# PCB-DISPARRAY4a.net
KiCad netlist of a schematic drawn in EAGLE
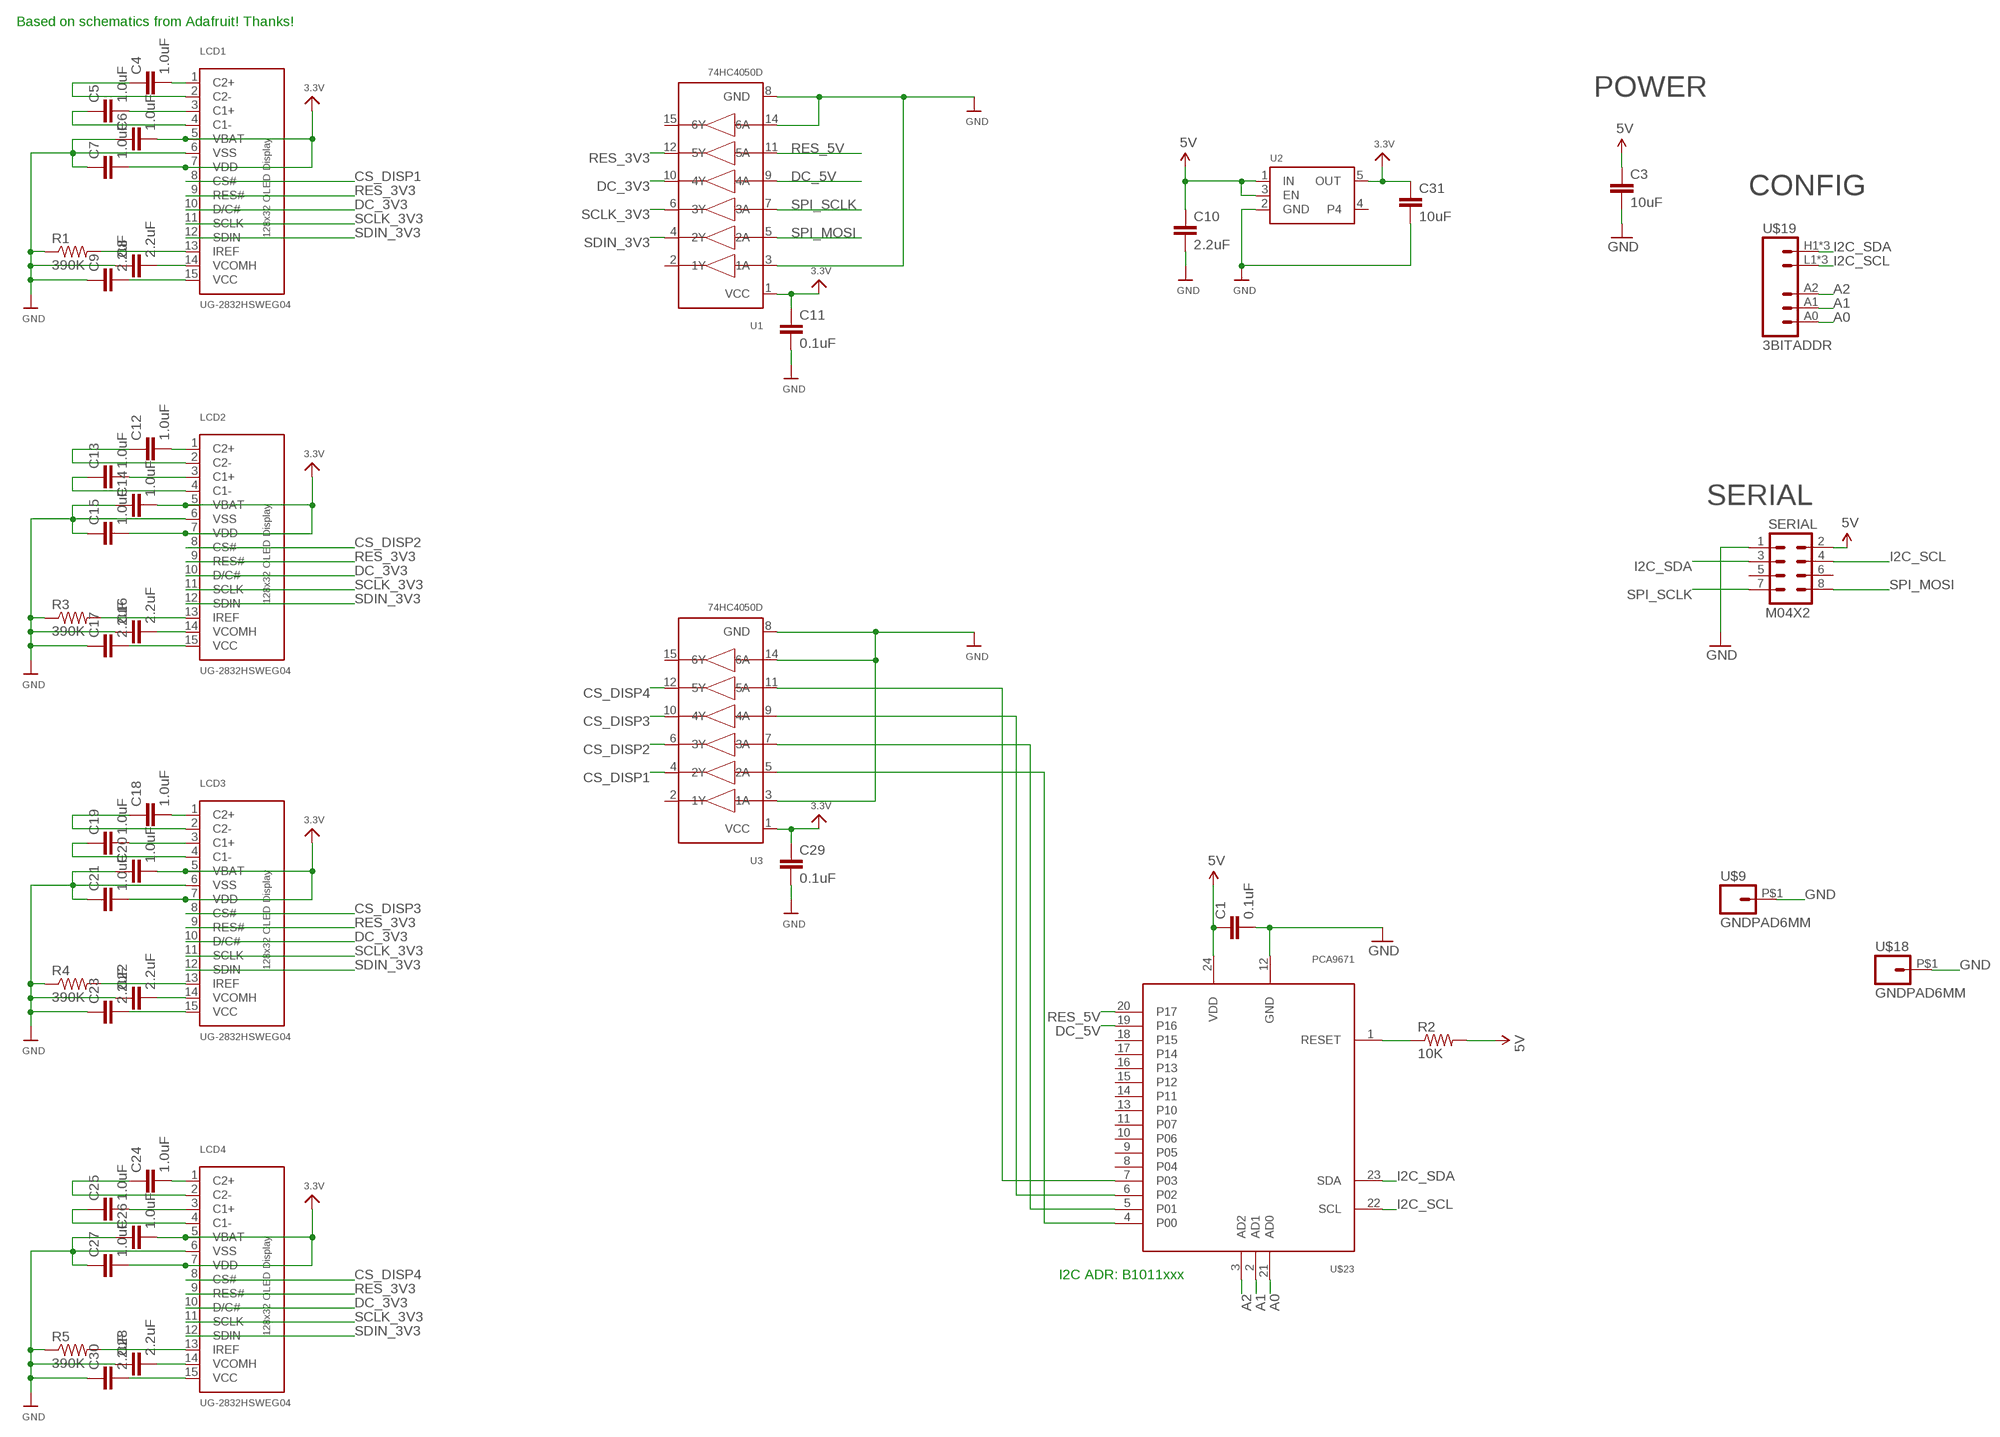
[diagram p0: schematic, sheet 1]

(export (version "E")
  (design (tool "Eeschema 10.0.6"))
  (components
    (comp (ref "C1")
      (value "0.1uF")
      (footprint "eagle-import:0603-CAP")
      (libsource (lib "eagle-import") (part "CAP0603-CAP"))
    )
    (comp (ref "C3")
      (value "10uF")
      (footprint "eagle-import:0805")
      (libsource (lib "eagle-import") (part "CAP0805"))
    )
    (comp (ref "C4")
      (value "1.0uF")
      (footprint "eagle-import:0603-CAP")
      (libsource (lib "eagle-import") (part "CAP0603-CAP"))
    )
    (comp (ref "C5")
      (value "1.0uF")
      (footprint "eagle-import:0603-CAP")
      (libsource (lib "eagle-import") (part "CAP0603-CAP"))
    )
    (comp (ref "C6")
      (value "1.0uF")
      (footprint "eagle-import:0603-CAP")
      (libsource (lib "eagle-import") (part "CAP0603-CAP"))
    )
    (comp (ref "C7")
      (value "1.0uF")
      (footprint "eagle-import:0603-CAP")
      (libsource (lib "eagle-import") (part "CAP0603-CAP"))
    )
    (comp (ref "C8")
      (value "2.2uF")
      (footprint "eagle-import:0603-CAP")
      (libsource (lib "eagle-import") (part "CAP0603-CAP"))
    )
    (comp (ref "C9")
      (value "2.2uF")
      (footprint "eagle-import:0603-CAP")
      (libsource (lib "eagle-import") (part "CAP0603-CAP"))
    )
    (comp (ref "C10")
      (value "2.2uF")
      (footprint "eagle-import:0805")
      (libsource (lib "eagle-import") (part "CAP0805"))
    )
    (comp (ref "C11")
      (value "0.1uF")
      (footprint "eagle-import:0603-CAP")
      (libsource (lib "eagle-import") (part "CAP0603-CAP"))
    )
    (comp (ref "C12")
      (value "1.0uF")
      (footprint "eagle-import:0603-CAP")
      (libsource (lib "eagle-import") (part "CAP0603-CAP"))
    )
    (comp (ref "C13")
      (value "1.0uF")
      (footprint "eagle-import:0603-CAP")
      (libsource (lib "eagle-import") (part "CAP0603-CAP"))
    )
    (comp (ref "C14")
      (value "1.0uF")
      (footprint "eagle-import:0603-CAP")
      (libsource (lib "eagle-import") (part "CAP0603-CAP"))
    )
    (comp (ref "C15")
      (value "1.0uF")
      (footprint "eagle-import:0603-CAP")
      (libsource (lib "eagle-import") (part "CAP0603-CAP"))
    )
    (comp (ref "C16")
      (value "2.2uF")
      (footprint "eagle-import:0603-CAP")
      (libsource (lib "eagle-import") (part "CAP0603-CAP"))
    )
    (comp (ref "C17")
      (value "2.2uF")
      (footprint "eagle-import:0603-CAP")
      (libsource (lib "eagle-import") (part "CAP0603-CAP"))
    )
    (comp (ref "C18")
      (value "1.0uF")
      (footprint "eagle-import:0603-CAP")
      (libsource (lib "eagle-import") (part "CAP0603-CAP"))
    )
    (comp (ref "C19")
      (value "1.0uF")
      (footprint "eagle-import:0603-CAP")
      (libsource (lib "eagle-import") (part "CAP0603-CAP"))
    )
    (comp (ref "C20")
      (value "1.0uF")
      (footprint "eagle-import:0603-CAP")
      (libsource (lib "eagle-import") (part "CAP0603-CAP"))
    )
    (comp (ref "C21")
      (value "1.0uF")
      (footprint "eagle-import:0603-CAP")
      (libsource (lib "eagle-import") (part "CAP0603-CAP"))
    )
    (comp (ref "C22")
      (value "2.2uF")
      (footprint "eagle-import:0603-CAP")
      (libsource (lib "eagle-import") (part "CAP0603-CAP"))
    )
    (comp (ref "C23")
      (value "2.2uF")
      (footprint "eagle-import:0603-CAP")
      (libsource (lib "eagle-import") (part "CAP0603-CAP"))
    )
    (comp (ref "C24")
      (value "1.0uF")
      (footprint "eagle-import:0603-CAP")
      (libsource (lib "eagle-import") (part "CAP0603-CAP"))
    )
    (comp (ref "C25")
      (value "1.0uF")
      (footprint "eagle-import:0603-CAP")
      (libsource (lib "eagle-import") (part "CAP0603-CAP"))
    )
    (comp (ref "C26")
      (value "1.0uF")
      (footprint "eagle-import:0603-CAP")
      (libsource (lib "eagle-import") (part "CAP0603-CAP"))
    )
    (comp (ref "C27")
      (value "1.0uF")
      (footprint "eagle-import:0603-CAP")
      (libsource (lib "eagle-import") (part "CAP0603-CAP"))
    )
    (comp (ref "C28")
      (value "2.2uF")
      (footprint "eagle-import:0603-CAP")
      (libsource (lib "eagle-import") (part "CAP0603-CAP"))
    )
    (comp (ref "C29")
      (value "0.1uF")
      (footprint "eagle-import:0603-CAP")
      (libsource (lib "eagle-import") (part "CAP0603-CAP"))
    )
    (comp (ref "C30")
      (value "2.2uF")
      (footprint "eagle-import:0603-CAP")
      (libsource (lib "eagle-import") (part "CAP0603-CAP"))
    )
    (comp (ref "C31")
      (value "10uF")
      (footprint "eagle-import:0805")
      (libsource (lib "eagle-import") (part "CAP0805"))
    )
    (comp (ref "LCD1")
      (value "UG-2832HSWEG04")
      (footprint "eagle-import:UG-2832HSWEG04_WRAPAROUND")
      (libsource (lib "eagle-import") (part "OLED_UG-2832HSWEG04WRAPAROUND"))
    )
    (comp (ref "LCD2")
      (value "UG-2832HSWEG04")
      (footprint "eagle-import:UG-2832HSWEG04_WRAPAROUND")
      (libsource (lib "eagle-import") (part "OLED_UG-2832HSWEG04WRAPAROUND"))
    )
    (comp (ref "LCD3")
      (value "UG-2832HSWEG04")
      (footprint "eagle-import:UG-2832HSWEG04_WRAPAROUND")
      (libsource (lib "eagle-import") (part "OLED_UG-2832HSWEG04WRAPAROUND"))
    )
    (comp (ref "LCD4")
      (value "UG-2832HSWEG04")
      (footprint "eagle-import:UG-2832HSWEG04_WRAPAROUND")
      (libsource (lib "eagle-import") (part "OLED_UG-2832HSWEG04WRAPAROUND"))
    )
    (comp (ref "R1")
      (value "390K")
      (footprint "eagle-import:0603-RES")
      (libsource (lib "eagle-import") (part "RESISTOR0603-RES"))
    )
    (comp (ref "R2")
      (value "10K")
      (footprint "eagle-import:0603-RES")
      (libsource (lib "eagle-import") (part "RESISTOR0603-RES"))
    )
    (comp (ref "R3")
      (value "390K")
      (footprint "eagle-import:0603-RES")
      (libsource (lib "eagle-import") (part "RESISTOR0603-RES"))
    )
    (comp (ref "R4")
      (value "390K")
      (footprint "eagle-import:0603-RES")
      (libsource (lib "eagle-import") (part "RESISTOR0603-RES"))
    )
    (comp (ref "R5")
      (value "390K")
      (footprint "eagle-import:0603-RES")
      (libsource (lib "eagle-import") (part "RESISTOR0603-RES"))
    )
    (comp (ref "SERIAL")
      (value "M04X2")
      (footprint "eagle-import:2X4")
      (libsource (lib "eagle-import") (part "M04X2"))
    )
    (comp (ref "U$9")
      (value "GNDPAD6MM")
      (footprint "eagle-import:3.2MMPAD6MM")
      (libsource (lib "eagle-import") (part "GNDPAD6MM"))
    )
    (comp (ref "U$18")
      (value "GNDPAD6MM")
      (footprint "eagle-import:3.2MMPAD6MM")
      (libsource (lib "eagle-import") (part "GNDPAD6MM"))
    )
    (comp (ref "U$19")
      (value "3BITADDR")
      (footprint "eagle-import:3BITADDR")
      (libsource (lib "eagle-import") (part "3BITADDR"))
    )
    (comp (ref "U$23")
      (value "PCA9671")
      (footprint "eagle-import:TSSOP24")
      (libsource (lib "eagle-import") (part "PCA9671"))
    )
    (comp (ref "U1")
      (value "74HC4050D")
      (footprint "eagle-import:TSSOP16")
      (libsource (lib "eagle-import") (part "74HC4050DTSSOP16"))
    )
    (comp (ref "U2")
      (value "VREG_SOT23-5")
      (footprint "eagle-import:SOT23-5")
      (libsource (lib "eagle-import") (part "VREG_SOT23-5"))
    )
    (comp (ref "U3")
      (value "74HC4050D")
      (footprint "eagle-import:TSSOP16")
      (libsource (lib "eagle-import") (part "74HC4050DTSSOP16"))
    )
  )
  (nets
    (net (code "1") (name "3.3V") (class "Default")
      (node (ref "C11") (pin "1") (pinfunction "1_1") (pintype "passive"))
      (node (ref "C14") (pin "2") (pinfunction "2_2") (pintype "passive"))
      (node (ref "C15") (pin "2") (pinfunction "2_2") (pintype "passive"))
      (node (ref "C20") (pin "2") (pinfunction "2_2") (pintype "passive"))
      (node (ref "C21") (pin "2") (pinfunction "2_2") (pintype "passive"))
      (node (ref "C26") (pin "2") (pinfunction "2_2") (pintype "passive"))
      (node (ref "C27") (pin "2") (pinfunction "2_2") (pintype "passive"))
      (node (ref "C29") (pin "1") (pinfunction "1_1") (pintype "passive"))
      (node (ref "C31") (pin "1") (pinfunction "1_1") (pintype "passive"))
      (node (ref "C6") (pin "2") (pinfunction "2_2") (pintype "passive"))
      (node (ref "C7") (pin "2") (pinfunction "2_2") (pintype "passive"))
      (node (ref "LCD1") (pin "5") (pinfunction "VBAT_5") (pintype "bidirectional"))
      (node (ref "LCD1") (pin "7") (pinfunction "VDD_7") (pintype "bidirectional"))
      (node (ref "LCD2") (pin "5") (pinfunction "VBAT_5") (pintype "bidirectional"))
      (node (ref "LCD2") (pin "7") (pinfunction "VDD_7") (pintype "bidirectional"))
      (node (ref "LCD3") (pin "5") (pinfunction "VBAT_5") (pintype "bidirectional"))
      (node (ref "LCD3") (pin "7") (pinfunction "VDD_7") (pintype "bidirectional"))
      (node (ref "LCD4") (pin "5") (pinfunction "VBAT_5") (pintype "bidirectional"))
      (node (ref "LCD4") (pin "7") (pinfunction "VDD_7") (pintype "bidirectional"))
      (node (ref "U1") (pin "1") (pinfunction "VCC_1") (pintype "bidirectional"))
      (node (ref "U2") (pin "5") (pinfunction "OUT_5") (pintype "bidirectional"))
      (node (ref "U3") (pin "1") (pinfunction "VCC_1") (pintype "bidirectional"))
    )
    (net (code "2") (name "5V") (class "Default")
      (node (ref "C1") (pin "1") (pinfunction "1_1") (pintype "passive"))
      (node (ref "C10") (pin "1") (pinfunction "1_1") (pintype "passive"))
      (node (ref "C3") (pin "1") (pinfunction "1_1") (pintype "passive"))
      (node (ref "R2") (pin "2") (pinfunction "2_2") (pintype "passive"))
      (node (ref "SERIAL") (pin "2") (pinfunction "2_2") (pintype "passive"))
      (node (ref "U$23") (pin "24") (pinfunction "VDD_24") (pintype "power_in"))
      (node (ref "U2") (pin "1") (pinfunction "IN_1") (pintype "bidirectional"))
      (node (ref "U2") (pin "3") (pinfunction "EN_3") (pintype "bidirectional"))
    )
    (net (code "3") (name "A0") (class "Default")
      (node (ref "U$19") (pin "A0") (pinfunction "A0_A0") (pintype "passive"))
      (node (ref "U$23") (pin "21") (pinfunction "AD0_21") (pintype "input"))
    )
    (net (code "4") (name "A1") (class "Default")
      (node (ref "U$19") (pin "A1") (pinfunction "A1_A1") (pintype "passive"))
      (node (ref "U$23") (pin "2") (pinfunction "AD1_2") (pintype "input"))
    )
    (net (code "5") (name "A2") (class "Default")
      (node (ref "U$19") (pin "A2") (pinfunction "A2_A2") (pintype "passive"))
      (node (ref "U$23") (pin "3") (pinfunction "AD2_3") (pintype "input"))
    )
    (net (code "6") (name "CS_DISP1") (class "Default")
      (node (ref "LCD1") (pin "8") (pinfunction "CS#_8") (pintype "bidirectional"))
      (node (ref "U3") (pin "4") (pinfunction "2Y_4") (pintype "bidirectional"))
    )
    (net (code "7") (name "CS_DISP2") (class "Default")
      (node (ref "LCD2") (pin "8") (pinfunction "CS#_8") (pintype "bidirectional"))
      (node (ref "U3") (pin "6") (pinfunction "3Y_6") (pintype "bidirectional"))
    )
    (net (code "8") (name "CS_DISP3") (class "Default")
      (node (ref "LCD3") (pin "8") (pinfunction "CS#_8") (pintype "bidirectional"))
      (node (ref "U3") (pin "10") (pinfunction "4Y_10") (pintype "bidirectional"))
    )
    (net (code "9") (name "CS_DISP4") (class "Default")
      (node (ref "LCD4") (pin "8") (pinfunction "CS#_8") (pintype "bidirectional"))
      (node (ref "U3") (pin "12") (pinfunction "5Y_12") (pintype "bidirectional"))
    )
    (net (code "10") (name "DC_3V3") (class "Default")
      (node (ref "LCD1") (pin "10") (pinfunction "D/C#_10") (pintype "bidirectional"))
      (node (ref "LCD2") (pin "10") (pinfunction "D/C#_10") (pintype "bidirectional"))
      (node (ref "LCD3") (pin "10") (pinfunction "D/C#_10") (pintype "bidirectional"))
      (node (ref "LCD4") (pin "10") (pinfunction "D/C#_10") (pintype "bidirectional"))
      (node (ref "U1") (pin "10") (pinfunction "4Y_10") (pintype "bidirectional"))
    )
    (net (code "11") (name "DC_5V") (class "Default")
      (node (ref "U$23") (pin "19") (pinfunction "P16_19") (pintype "output"))
      (node (ref "U1") (pin "9") (pinfunction "4A_9") (pintype "bidirectional"))
    )
    (net (code "12") (name "GND") (class "Default")
      (node (ref "C1") (pin "2") (pinfunction "2_2") (pintype "passive"))
      (node (ref "C10") (pin "2") (pinfunction "2_2") (pintype "passive"))
      (node (ref "C11") (pin "2") (pinfunction "2_2") (pintype "passive"))
      (node (ref "C14") (pin "1") (pinfunction "1_1") (pintype "passive"))
      (node (ref "C15") (pin "1") (pinfunction "1_1") (pintype "passive"))
      (node (ref "C16") (pin "1") (pinfunction "1_1") (pintype "passive"))
      (node (ref "C17") (pin "1") (pinfunction "1_1") (pintype "passive"))
      (node (ref "C20") (pin "1") (pinfunction "1_1") (pintype "passive"))
      (node (ref "C21") (pin "1") (pinfunction "1_1") (pintype "passive"))
      (node (ref "C22") (pin "1") (pinfunction "1_1") (pintype "passive"))
      (node (ref "C23") (pin "1") (pinfunction "1_1") (pintype "passive"))
      (node (ref "C26") (pin "1") (pinfunction "1_1") (pintype "passive"))
      (node (ref "C27") (pin "1") (pinfunction "1_1") (pintype "passive"))
      (node (ref "C28") (pin "1") (pinfunction "1_1") (pintype "passive"))
      (node (ref "C29") (pin "2") (pinfunction "2_2") (pintype "passive"))
      (node (ref "C3") (pin "2") (pinfunction "2_2") (pintype "passive"))
      (node (ref "C30") (pin "1") (pinfunction "1_1") (pintype "passive"))
      (node (ref "C31") (pin "2") (pinfunction "2_2") (pintype "passive"))
      (node (ref "C6") (pin "1") (pinfunction "1_1") (pintype "passive"))
      (node (ref "C7") (pin "1") (pinfunction "1_1") (pintype "passive"))
      (node (ref "C8") (pin "1") (pinfunction "1_1") (pintype "passive"))
      (node (ref "C9") (pin "1") (pinfunction "1_1") (pintype "passive"))
      (node (ref "LCD1") (pin "6") (pinfunction "VSS_6") (pintype "bidirectional"))
      (node (ref "LCD2") (pin "6") (pinfunction "VSS_6") (pintype "bidirectional"))
      (node (ref "LCD3") (pin "6") (pinfunction "VSS_6") (pintype "bidirectional"))
      (node (ref "LCD4") (pin "6") (pinfunction "VSS_6") (pintype "bidirectional"))
      (node (ref "R1") (pin "1") (pinfunction "1_1") (pintype "passive"))
      (node (ref "R3") (pin "1") (pinfunction "1_1") (pintype "passive"))
      (node (ref "R4") (pin "1") (pinfunction "1_1") (pintype "passive"))
      (node (ref "R5") (pin "1") (pinfunction "1_1") (pintype "passive"))
      (node (ref "SERIAL") (pin "1") (pinfunction "1_1") (pintype "passive"))
      (node (ref "U$18") (pin "P$1") (pinfunction "1_P$1") (pintype "passive"))
      (node (ref "U$23") (pin "12") (pinfunction "GND_12") (pintype "power_in"))
      (node (ref "U$9") (pin "P$1") (pinfunction "1_P$1") (pintype "passive"))
      (node (ref "U1") (pin "14") (pinfunction "6A_14") (pintype "bidirectional"))
      (node (ref "U1") (pin "3") (pinfunction "1A_3") (pintype "bidirectional"))
      (node (ref "U1") (pin "8") (pinfunction "GND_8") (pintype "bidirectional"))
      (node (ref "U2") (pin "2") (pinfunction "GND_2") (pintype "bidirectional"))
      (node (ref "U3") (pin "14") (pinfunction "6A_14") (pintype "bidirectional"))
      (node (ref "U3") (pin "3") (pinfunction "1A_3") (pintype "bidirectional"))
      (node (ref "U3") (pin "8") (pinfunction "GND_8") (pintype "bidirectional"))
    )
    (net (code "13") (name "I2C_SCL") (class "Default")
      (node (ref "SERIAL") (pin "4") (pinfunction "4_4") (pintype "passive"))
      (node (ref "U$19") (pin "L1") (pinfunction "GND_L1") (pintype "passive"))
      (node (ref "U$19") (pin "L2") (pinfunction "GND_L2") (pintype "passive"))
      (node (ref "U$19") (pin "L3") (pinfunction "GND_L3") (pintype "passive"))
      (node (ref "U$23") (pin "22") (pinfunction "SCL_22") (pintype "input"))
    )
    (net (code "14") (name "I2C_SDA") (class "Default")
      (node (ref "SERIAL") (pin "3") (pinfunction "3_3") (pintype "passive"))
      (node (ref "U$19") (pin "H1") (pinfunction "VCC_H1") (pintype "passive"))
      (node (ref "U$19") (pin "H2") (pinfunction "VCC_H2") (pintype "passive"))
      (node (ref "U$19") (pin "H3") (pinfunction "VCC_H3") (pintype "passive"))
      (node (ref "U$23") (pin "23") (pinfunction "SDA_23") (pintype "input"))
    )
    (net (code "15") (name "Net-(LCD1-C1+)") (class "Default")
      (node (ref "C5") (pin "2") (pinfunction "2_2") (pintype "passive"))
      (node (ref "LCD1") (pin "3") (pinfunction "C1+_3") (pintype "bidirectional"))
    )
    (net (code "16") (name "Net-(LCD1-C1-)") (class "Default")
      (node (ref "C5") (pin "1") (pinfunction "1_1") (pintype "passive"))
      (node (ref "LCD1") (pin "4") (pinfunction "C1-_4") (pintype "bidirectional"))
    )
    (net (code "17") (name "Net-(LCD1-C2+)") (class "Default")
      (node (ref "C4") (pin "2") (pinfunction "2_2") (pintype "passive"))
      (node (ref "LCD1") (pin "1") (pinfunction "C2+_1") (pintype "bidirectional"))
    )
    (net (code "18") (name "Net-(LCD1-C2-)") (class "Default")
      (node (ref "C4") (pin "1") (pinfunction "1_1") (pintype "passive"))
      (node (ref "LCD1") (pin "2") (pinfunction "C2-_2") (pintype "bidirectional"))
    )
    (net (code "19") (name "Net-(LCD1-IREF)") (class "Default")
      (node (ref "LCD1") (pin "13") (pinfunction "IREF_13") (pintype "bidirectional"))
      (node (ref "R1") (pin "2") (pinfunction "2_2") (pintype "passive"))
    )
    (net (code "20") (name "Net-(LCD1-VCC)") (class "Default")
      (node (ref "C9") (pin "2") (pinfunction "2_2") (pintype "passive"))
      (node (ref "LCD1") (pin "15") (pinfunction "VCC_15") (pintype "bidirectional"))
    )
    (net (code "21") (name "Net-(LCD1-VCOMH)") (class "Default")
      (node (ref "C8") (pin "2") (pinfunction "2_2") (pintype "passive"))
      (node (ref "LCD1") (pin "14") (pinfunction "VCOMH_14") (pintype "bidirectional"))
    )
    (net (code "22") (name "Net-(LCD2-C1+)") (class "Default")
      (node (ref "C13") (pin "2") (pinfunction "2_2") (pintype "passive"))
      (node (ref "LCD2") (pin "3") (pinfunction "C1+_3") (pintype "bidirectional"))
    )
    (net (code "23") (name "Net-(LCD2-C1-)") (class "Default")
      (node (ref "C13") (pin "1") (pinfunction "1_1") (pintype "passive"))
      (node (ref "LCD2") (pin "4") (pinfunction "C1-_4") (pintype "bidirectional"))
    )
    (net (code "24") (name "Net-(LCD2-C2+)") (class "Default")
      (node (ref "C12") (pin "2") (pinfunction "2_2") (pintype "passive"))
      (node (ref "LCD2") (pin "1") (pinfunction "C2+_1") (pintype "bidirectional"))
    )
    (net (code "25") (name "Net-(LCD2-C2-)") (class "Default")
      (node (ref "C12") (pin "1") (pinfunction "1_1") (pintype "passive"))
      (node (ref "LCD2") (pin "2") (pinfunction "C2-_2") (pintype "bidirectional"))
    )
    (net (code "26") (name "Net-(LCD2-IREF)") (class "Default")
      (node (ref "LCD2") (pin "13") (pinfunction "IREF_13") (pintype "bidirectional"))
      (node (ref "R3") (pin "2") (pinfunction "2_2") (pintype "passive"))
    )
    (net (code "27") (name "Net-(LCD2-VCC)") (class "Default")
      (node (ref "C17") (pin "2") (pinfunction "2_2") (pintype "passive"))
      (node (ref "LCD2") (pin "15") (pinfunction "VCC_15") (pintype "bidirectional"))
    )
    (net (code "28") (name "Net-(LCD2-VCOMH)") (class "Default")
      (node (ref "C16") (pin "2") (pinfunction "2_2") (pintype "passive"))
      (node (ref "LCD2") (pin "14") (pinfunction "VCOMH_14") (pintype "bidirectional"))
    )
    (net (code "29") (name "Net-(LCD3-C1+)") (class "Default")
      (node (ref "C19") (pin "2") (pinfunction "2_2") (pintype "passive"))
      (node (ref "LCD3") (pin "3") (pinfunction "C1+_3") (pintype "bidirectional"))
    )
    (net (code "30") (name "Net-(LCD3-C1-)") (class "Default")
      (node (ref "C19") (pin "1") (pinfunction "1_1") (pintype "passive"))
      (node (ref "LCD3") (pin "4") (pinfunction "C1-_4") (pintype "bidirectional"))
    )
    (net (code "31") (name "Net-(LCD3-C2+)") (class "Default")
      (node (ref "C18") (pin "2") (pinfunction "2_2") (pintype "passive"))
      (node (ref "LCD3") (pin "1") (pinfunction "C2+_1") (pintype "bidirectional"))
    )
    (net (code "32") (name "Net-(LCD3-C2-)") (class "Default")
      (node (ref "C18") (pin "1") (pinfunction "1_1") (pintype "passive"))
      (node (ref "LCD3") (pin "2") (pinfunction "C2-_2") (pintype "bidirectional"))
    )
    (net (code "33") (name "Net-(LCD3-IREF)") (class "Default")
      (node (ref "LCD3") (pin "13") (pinfunction "IREF_13") (pintype "bidirectional"))
      (node (ref "R4") (pin "2") (pinfunction "2_2") (pintype "passive"))
    )
    (net (code "34") (name "Net-(LCD3-VCC)") (class "Default")
      (node (ref "C23") (pin "2") (pinfunction "2_2") (pintype "passive"))
      (node (ref "LCD3") (pin "15") (pinfunction "VCC_15") (pintype "bidirectional"))
    )
    (net (code "35") (name "Net-(LCD3-VCOMH)") (class "Default")
      (node (ref "C22") (pin "2") (pinfunction "2_2") (pintype "passive"))
      (node (ref "LCD3") (pin "14") (pinfunction "VCOMH_14") (pintype "bidirectional"))
    )
    (net (code "36") (name "Net-(LCD4-C1+)") (class "Default")
      (node (ref "C25") (pin "2") (pinfunction "2_2") (pintype "passive"))
      (node (ref "LCD4") (pin "3") (pinfunction "C1+_3") (pintype "bidirectional"))
    )
    (net (code "37") (name "Net-(LCD4-C1-)") (class "Default")
      (node (ref "C25") (pin "1") (pinfunction "1_1") (pintype "passive"))
      (node (ref "LCD4") (pin "4") (pinfunction "C1-_4") (pintype "bidirectional"))
    )
    (net (code "38") (name "Net-(LCD4-C2+)") (class "Default")
      (node (ref "C24") (pin "2") (pinfunction "2_2") (pintype "passive"))
      (node (ref "LCD4") (pin "1") (pinfunction "C2+_1") (pintype "bidirectional"))
    )
    (net (code "39") (name "Net-(LCD4-C2-)") (class "Default")
      (node (ref "C24") (pin "1") (pinfunction "1_1") (pintype "passive"))
      (node (ref "LCD4") (pin "2") (pinfunction "C2-_2") (pintype "bidirectional"))
    )
    (net (code "40") (name "Net-(LCD4-IREF)") (class "Default")
      (node (ref "LCD4") (pin "13") (pinfunction "IREF_13") (pintype "bidirectional"))
      (node (ref "R5") (pin "2") (pinfunction "2_2") (pintype "passive"))
    )
    (net (code "41") (name "Net-(LCD4-VCC)") (class "Default")
      (node (ref "C30") (pin "2") (pinfunction "2_2") (pintype "passive"))
      (node (ref "LCD4") (pin "15") (pinfunction "VCC_15") (pintype "bidirectional"))
    )
    (net (code "42") (name "Net-(LCD4-VCOMH)") (class "Default")
      (node (ref "C28") (pin "2") (pinfunction "2_2") (pintype "passive"))
      (node (ref "LCD4") (pin "14") (pinfunction "VCOMH_14") (pintype "bidirectional"))
    )
    (net (code "43") (name "Net-(U$23-P00)") (class "Default")
      (node (ref "U$23") (pin "4") (pinfunction "P00_4") (pintype "output"))
      (node (ref "U3") (pin "5") (pinfunction "2A_5") (pintype "bidirectional"))
    )
    (net (code "44") (name "Net-(U$23-P01)") (class "Default")
      (node (ref "U$23") (pin "5") (pinfunction "P01_5") (pintype "output"))
      (node (ref "U3") (pin "7") (pinfunction "3A_7") (pintype "bidirectional"))
    )
    (net (code "45") (name "Net-(U$23-P02)") (class "Default")
      (node (ref "U$23") (pin "6") (pinfunction "P02_6") (pintype "output"))
      (node (ref "U3") (pin "9") (pinfunction "4A_9") (pintype "bidirectional"))
    )
    (net (code "46") (name "Net-(U$23-P03)") (class "Default")
      (node (ref "U$23") (pin "7") (pinfunction "P03_7") (pintype "output"))
      (node (ref "U3") (pin "11") (pinfunction "5A_11") (pintype "bidirectional"))
    )
    (net (code "47") (name "Net-(U$23-RESET)") (class "Default")
      (node (ref "R2") (pin "1") (pinfunction "1_1") (pintype "passive"))
      (node (ref "U$23") (pin "1") (pinfunction "RESET_1") (pintype "input"))
    )
    (net (code "48") (name "RES_3V3") (class "Default")
      (node (ref "LCD1") (pin "9") (pinfunction "RES#_9") (pintype "bidirectional"))
      (node (ref "LCD2") (pin "9") (pinfunction "RES#_9") (pintype "bidirectional"))
      (node (ref "LCD3") (pin "9") (pinfunction "RES#_9") (pintype "bidirectional"))
      (node (ref "LCD4") (pin "9") (pinfunction "RES#_9") (pintype "bidirectional"))
      (node (ref "U1") (pin "12") (pinfunction "5Y_12") (pintype "bidirectional"))
    )
    (net (code "49") (name "RES_5V") (class "Default")
      (node (ref "U$23") (pin "20") (pinfunction "P17_20") (pintype "output"))
      (node (ref "U1") (pin "11") (pinfunction "5A_11") (pintype "bidirectional"))
    )
    (net (code "50") (name "SCLK_3V3") (class "Default")
      (node (ref "LCD1") (pin "11") (pinfunction "SCLK_11") (pintype "bidirectional"))
      (node (ref "LCD2") (pin "11") (pinfunction "SCLK_11") (pintype "bidirectional"))
      (node (ref "LCD3") (pin "11") (pinfunction "SCLK_11") (pintype "bidirectional"))
      (node (ref "LCD4") (pin "11") (pinfunction "SCLK_11") (pintype "bidirectional"))
      (node (ref "U1") (pin "6") (pinfunction "3Y_6") (pintype "bidirectional"))
    )
    (net (code "51") (name "SDIN_3V3") (class "Default")
      (node (ref "LCD1") (pin "12") (pinfunction "SDIN_12") (pintype "bidirectional"))
      (node (ref "LCD2") (pin "12") (pinfunction "SDIN_12") (pintype "bidirectional"))
      (node (ref "LCD3") (pin "12") (pinfunction "SDIN_12") (pintype "bidirectional"))
      (node (ref "LCD4") (pin "12") (pinfunction "SDIN_12") (pintype "bidirectional"))
      (node (ref "U1") (pin "4") (pinfunction "2Y_4") (pintype "bidirectional"))
    )
    (net (code "52") (name "SPI_MOSI") (class "Default")
      (node (ref "SERIAL") (pin "8") (pinfunction "8_8") (pintype "passive"))
      (node (ref "U1") (pin "5") (pinfunction "2A_5") (pintype "bidirectional"))
    )
    (net (code "53") (name "SPI_SCLK") (class "Default")
      (node (ref "SERIAL") (pin "7") (pinfunction "7_7") (pintype "passive"))
      (node (ref "U1") (pin "7") (pinfunction "3A_7") (pintype "bidirectional"))
    )
    (net (code "54") (name "unconnected-(SERIAL-Pad5)") (class "Default")
      (node (ref "SERIAL") (pin "5") (pinfunction "5_5") (pintype "passive"))
    )
    (net (code "55") (name "unconnected-(SERIAL-Pad6)") (class "Default")
      (node (ref "SERIAL") (pin "6") (pinfunction "6_6") (pintype "passive"))
    )
    (net (code "56") (name "unconnected-(U$23-P04-Pad8)") (class "Default")
      (node (ref "U$23") (pin "8") (pinfunction "P04_8") (pintype "output"))
    )
    (net (code "57") (name "unconnected-(U$23-P05-Pad9)") (class "Default")
      (node (ref "U$23") (pin "9") (pinfunction "P05_9") (pintype "output"))
    )
    (net (code "58") (name "unconnected-(U$23-P06-Pad10)") (class "Default")
      (node (ref "U$23") (pin "10") (pinfunction "P06_10") (pintype "output"))
    )
    (net (code "59") (name "unconnected-(U$23-P07-Pad11)") (class "Default")
      (node (ref "U$23") (pin "11") (pinfunction "P07_11") (pintype "output"))
    )
    (net (code "60") (name "unconnected-(U$23-P10-Pad13)") (class "Default")
      (node (ref "U$23") (pin "13") (pinfunction "P10_13") (pintype "output"))
    )
    (net (code "61") (name "unconnected-(U$23-P11-Pad14)") (class "Default")
      (node (ref "U$23") (pin "14") (pinfunction "P11_14") (pintype "output"))
    )
    (net (code "62") (name "unconnected-(U$23-P12-Pad15)") (class "Default")
      (node (ref "U$23") (pin "15") (pinfunction "P12_15") (pintype "output"))
    )
    (net (code "63") (name "unconnected-(U$23-P13-Pad16)") (class "Default")
      (node (ref "U$23") (pin "16") (pinfunction "P13_16") (pintype "output"))
    )
    (net (code "64") (name "unconnected-(U$23-P14-Pad17)") (class "Default")
      (node (ref "U$23") (pin "17") (pinfunction "P14_17") (pintype "output"))
    )
    (net (code "65") (name "unconnected-(U$23-P15-Pad18)") (class "Default")
      (node (ref "U$23") (pin "18") (pinfunction "P15_18") (pintype "output"))
    )
    (net (code "66") (name "unconnected-(U1-1Y-Pad2)") (class "Default")
      (node (ref "U1") (pin "2") (pinfunction "1Y_2") (pintype "bidirectional"))
    )
    (net (code "67") (name "unconnected-(U1-6Y-Pad15)") (class "Default")
      (node (ref "U1") (pin "15") (pinfunction "6Y_15") (pintype "bidirectional"))
    )
    (net (code "68") (name "unconnected-(U2-P4-Pad4)") (class "Default")
      (node (ref "U2") (pin "4") (pinfunction "P4_4") (pintype "bidirectional"))
    )
    (net (code "69") (name "unconnected-(U3-1Y-Pad2)") (class "Default")
      (node (ref "U3") (pin "2") (pinfunction "1Y_2") (pintype "bidirectional"))
    )
    (net (code "70") (name "unconnected-(U3-6Y-Pad15)") (class "Default")
      (node (ref "U3") (pin "15") (pinfunction "6Y_15") (pintype "bidirectional"))
    )
  )
)
